# Resonator_ISTA.net
KiCad netlist of a schematic drawn in EAGLE
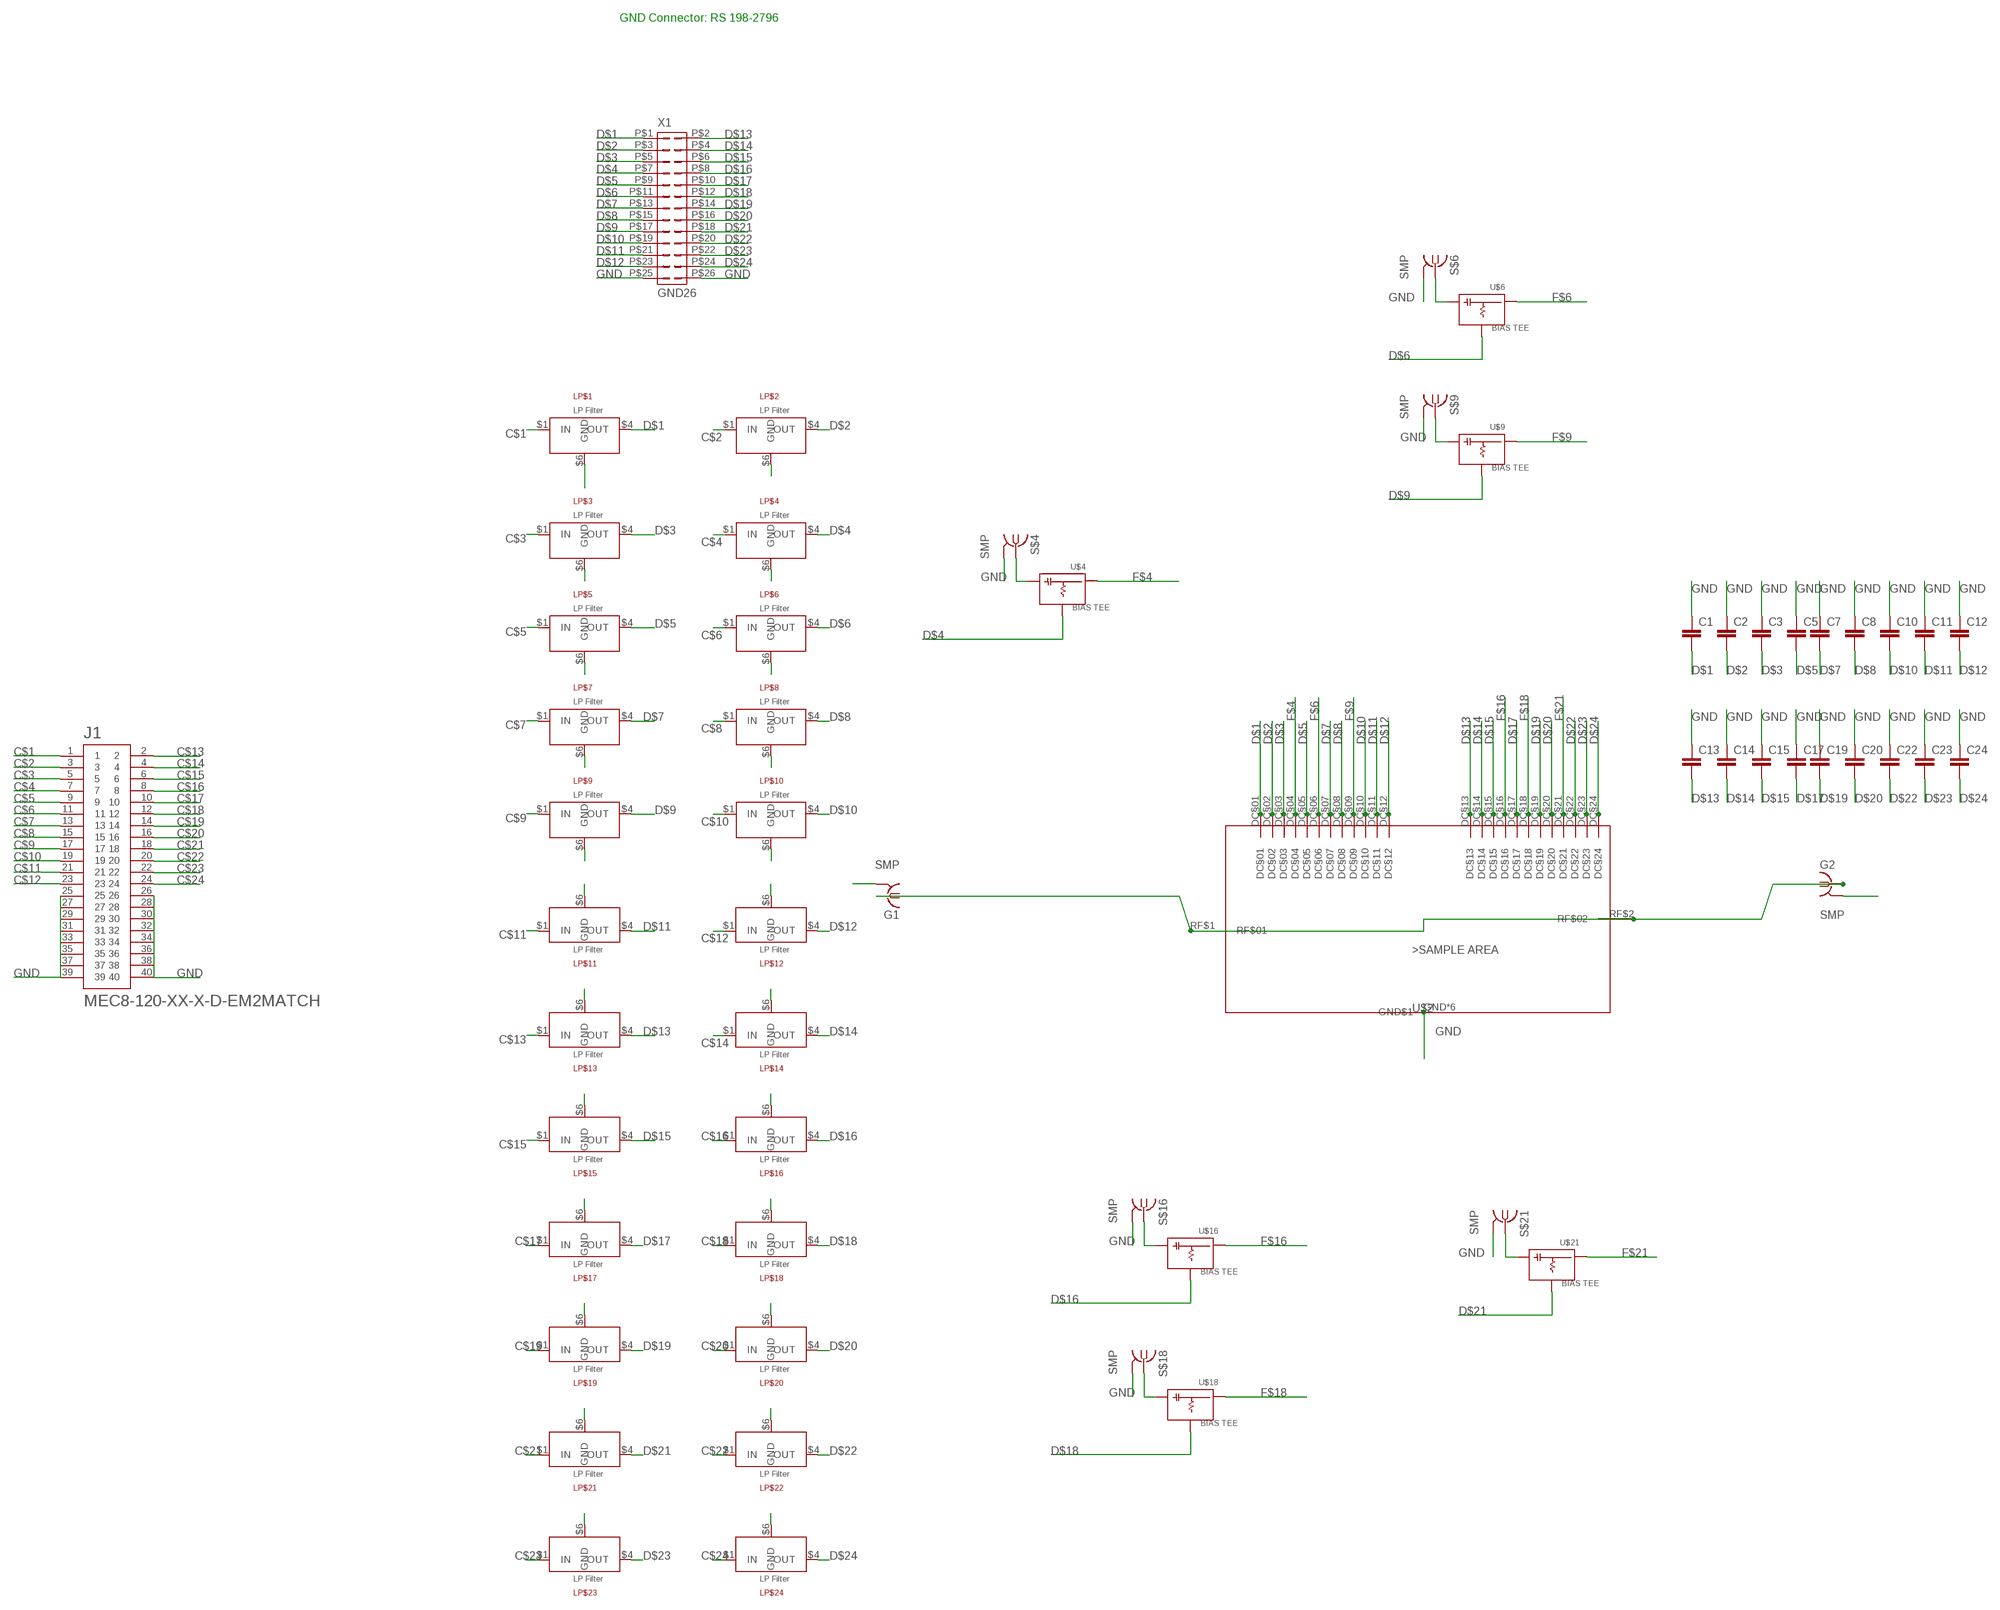
[diagram p0: schematic, sheet 1]

(export (version "E")
  (design (tool "Eeschema 10.0.6"))
  (components
    (comp (ref "C1")
      (value "C-EUC0805K")
      (footprint "eagle-import:C0805K")
      (libsource (lib "eagle-import") (part "C-EUC0805K"))
    )
    (comp (ref "C2")
      (value "C-EUC0805K")
      (footprint "eagle-import:C0805K")
      (libsource (lib "eagle-import") (part "C-EUC0805K"))
    )
    (comp (ref "C3")
      (value "C-EUC0805K")
      (footprint "eagle-import:C0805K")
      (libsource (lib "eagle-import") (part "C-EUC0805K"))
    )
    (comp (ref "C5")
      (value "C-EUC0805K")
      (footprint "eagle-import:C0805K")
      (libsource (lib "eagle-import") (part "C-EUC0805K"))
    )
    (comp (ref "C7")
      (value "C-EUC0805K")
      (footprint "eagle-import:C0805K")
      (libsource (lib "eagle-import") (part "C-EUC0805K"))
    )
    (comp (ref "C8")
      (value "C-EUC0805K")
      (footprint "eagle-import:C0805K")
      (libsource (lib "eagle-import") (part "C-EUC0805K"))
    )
    (comp (ref "C10")
      (value "C-EUC0805K")
      (footprint "eagle-import:C0805K")
      (libsource (lib "eagle-import") (part "C-EUC0805K"))
    )
    (comp (ref "C11")
      (value "C-EUC0805K")
      (footprint "eagle-import:C0805K")
      (libsource (lib "eagle-import") (part "C-EUC0805K"))
    )
    (comp (ref "C12")
      (value "C-EUC0805K")
      (footprint "eagle-import:C0805K")
      (libsource (lib "eagle-import") (part "C-EUC0805K"))
    )
    (comp (ref "C13")
      (value "C-EUC0805K")
      (footprint "eagle-import:C0805K")
      (libsource (lib "eagle-import") (part "C-EUC0805K"))
    )
    (comp (ref "C14")
      (value "C-EUC0805K")
      (footprint "eagle-import:C0805K")
      (libsource (lib "eagle-import") (part "C-EUC0805K"))
    )
    (comp (ref "C15")
      (value "C-EUC0805K")
      (footprint "eagle-import:C0805K")
      (libsource (lib "eagle-import") (part "C-EUC0805K"))
    )
    (comp (ref "C17")
      (value "C-EUC0805K")
      (footprint "eagle-import:C0805K")
      (libsource (lib "eagle-import") (part "C-EUC0805K"))
    )
    (comp (ref "C19")
      (value "C-EUC0805K")
      (footprint "eagle-import:C0805K")
      (libsource (lib "eagle-import") (part "C-EUC0805K"))
    )
    (comp (ref "C20")
      (value "C-EUC0805K")
      (footprint "eagle-import:C0805K")
      (libsource (lib "eagle-import") (part "C-EUC0805K"))
    )
    (comp (ref "C22")
      (value "C-EUC0805K")
      (footprint "eagle-import:C0805K")
      (libsource (lib "eagle-import") (part "C-EUC0805K"))
    )
    (comp (ref "C23")
      (value "C-EUC0805K")
      (footprint "eagle-import:C0805K")
      (libsource (lib "eagle-import") (part "C-EUC0805K"))
    )
    (comp (ref "C24")
      (value "C-EUC0805K")
      (footprint "eagle-import:C0805K")
      (libsource (lib "eagle-import") (part "C-EUC0805K"))
    )
    (comp (ref "G1")
      (value "MC-921")
      (footprint "eagle-import:SMP_STRAIGHT_MINI_WIDE_V1_01_ROUND")
      (libsource (lib "eagle-import") (part "MC-921"))
    )
    (comp (ref "G2")
      (value "MC-921")
      (footprint "eagle-import:SMP_STRAIGHT_MINI_WIDE_V1_01_ROUND")
      (libsource (lib "eagle-import") (part "MC-921"))
    )
    (comp (ref "J1")
      (value "MEC8-120-XX-X-D-EM2MATCH")
      (footprint "eagle-import:SAMTEC_MEC8-120-XX-X-D-EM2_MATCH")
      (libsource (lib "eagle-import") (part "MEC8-120-XX-X-D-EM2MATCH"))
    )
    (comp (ref "LP$1")
      (value "LP-FILTER/1-STAGETOP")
      (footprint "eagle-import:LP-FILTER_1_STAGE_OS_0603_TOP")
      (libsource (lib "eagle-import") (part "LP-FILTER/1-STAGETOP"))
    )
    (comp (ref "LP$2")
      (value "LP-FILTER/1-STAGETOP")
      (footprint "eagle-import:LP-FILTER_1_STAGE_OS_0603_TOP")
      (libsource (lib "eagle-import") (part "LP-FILTER/1-STAGETOP"))
    )
    (comp (ref "LP$3")
      (value "LP-FILTER/1-STAGEBOT")
      (footprint "eagle-import:LP-FILTER_1_STAGE_OS_0603_BOTTOM")
      (libsource (lib "eagle-import") (part "LP-FILTER/1-STAGEBOT"))
    )
    (comp (ref "LP$4")
      (value "LP-FILTER/1-STAGEBOT")
      (footprint "eagle-import:LP-FILTER_1_STAGE_OS_0603_BOTTOM")
      (libsource (lib "eagle-import") (part "LP-FILTER/1-STAGEBOT"))
    )
    (comp (ref "LP$5")
      (value "LP-FILTER/1-STAGEBOT")
      (footprint "eagle-import:LP-FILTER_1_STAGE_OS_0603_BOTTOM")
      (libsource (lib "eagle-import") (part "LP-FILTER/1-STAGEBOT"))
    )
    (comp (ref "LP$6")
      (value "LP-FILTER/1-STAGEBOT")
      (footprint "eagle-import:LP-FILTER_1_STAGE_OS_0603_BOTTOM")
      (libsource (lib "eagle-import") (part "LP-FILTER/1-STAGEBOT"))
    )
    (comp (ref "LP$7")
      (value "LP-FILTER/1-STAGEBOT")
      (footprint "eagle-import:LP-FILTER_1_STAGE_OS_0603_BOTTOM")
      (libsource (lib "eagle-import") (part "LP-FILTER/1-STAGEBOT"))
    )
    (comp (ref "LP$8")
      (value "LP-FILTER/1-STAGEBOT")
      (footprint "eagle-import:LP-FILTER_1_STAGE_OS_0603_BOTTOM")
      (libsource (lib "eagle-import") (part "LP-FILTER/1-STAGEBOT"))
    )
    (comp (ref "LP$9")
      (value "LP-FILTER/1-STAGETOP")
      (footprint "eagle-import:LP-FILTER_1_STAGE_OS_0603_TOP")
      (libsource (lib "eagle-import") (part "LP-FILTER/1-STAGETOP"))
    )
    (comp (ref "LP$10")
      (value "LP-FILTER/1-STAGETOP")
      (footprint "eagle-import:LP-FILTER_1_STAGE_OS_0603_TOP")
      (libsource (lib "eagle-import") (part "LP-FILTER/1-STAGETOP"))
    )
    (comp (ref "LP$11")
      (value "LP-FILTER/1-STAGETOP")
      (footprint "eagle-import:LP-FILTER_1_STAGE_OS_0603_TOP")
      (libsource (lib "eagle-import") (part "LP-FILTER/1-STAGETOP"))
    )
    (comp (ref "LP$12")
      (value "LP-FILTER/1-STAGETOP")
      (footprint "eagle-import:LP-FILTER_1_STAGE_OS_0603_TOP")
      (libsource (lib "eagle-import") (part "LP-FILTER/1-STAGETOP"))
    )
    (comp (ref "LP$13")
      (value "LP-FILTER/1-STAGETOP")
      (footprint "eagle-import:LP-FILTER_1_STAGE_OS_0603_TOP")
      (libsource (lib "eagle-import") (part "LP-FILTER/1-STAGETOP"))
    )
    (comp (ref "LP$14")
      (value "LP-FILTER/1-STAGETOP")
      (footprint "eagle-import:LP-FILTER_1_STAGE_OS_0603_TOP")
      (libsource (lib "eagle-import") (part "LP-FILTER/1-STAGETOP"))
    )
    (comp (ref "LP$15")
      (value "LP-FILTER/1-STAGETOP")
      (footprint "eagle-import:LP-FILTER_1_STAGE_OS_0603_TOP")
      (libsource (lib "eagle-import") (part "LP-FILTER/1-STAGETOP"))
    )
    (comp (ref "LP$16")
      (value "LP-FILTER/1-STAGETOP")
      (footprint "eagle-import:LP-FILTER_1_STAGE_OS_0603_TOP")
      (libsource (lib "eagle-import") (part "LP-FILTER/1-STAGETOP"))
    )
    (comp (ref "LP$17")
      (value "LP-FILTER/1-STAGETOP")
      (footprint "eagle-import:LP-FILTER_1_STAGE_OS_0603_TOP")
      (libsource (lib "eagle-import") (part "LP-FILTER/1-STAGETOP"))
    )
    (comp (ref "LP$18")
      (value "LP-FILTER/1-STAGETOP")
      (footprint "eagle-import:LP-FILTER_1_STAGE_OS_0603_TOP")
      (libsource (lib "eagle-import") (part "LP-FILTER/1-STAGETOP"))
    )
    (comp (ref "LP$19")
      (value "LP-FILTER/1-STAGETOP")
      (footprint "eagle-import:LP-FILTER_1_STAGE_OS_0603_TOP")
      (libsource (lib "eagle-import") (part "LP-FILTER/1-STAGETOP"))
    )
    (comp (ref "LP$20")
      (value "LP-FILTER/1-STAGETOP")
      (footprint "eagle-import:LP-FILTER_1_STAGE_OS_0603_TOP")
      (libsource (lib "eagle-import") (part "LP-FILTER/1-STAGETOP"))
    )
    (comp (ref "LP$21")
      (value "LP-FILTER/1-STAGETOP")
      (footprint "eagle-import:LP-FILTER_1_STAGE_OS_0603_TOP")
      (libsource (lib "eagle-import") (part "LP-FILTER/1-STAGETOP"))
    )
    (comp (ref "LP$22")
      (value "LP-FILTER/1-STAGETOP")
      (footprint "eagle-import:LP-FILTER_1_STAGE_OS_0603_TOP")
      (libsource (lib "eagle-import") (part "LP-FILTER/1-STAGETOP"))
    )
    (comp (ref "LP$23")
      (value "LP-FILTER/1-STAGETOP")
      (footprint "eagle-import:LP-FILTER_1_STAGE_OS_0603_TOP")
      (libsource (lib "eagle-import") (part "LP-FILTER/1-STAGETOP"))
    )
    (comp (ref "LP$24")
      (value "LP-FILTER/1-STAGETOP")
      (footprint "eagle-import:LP-FILTER_1_STAGE_OS_0603_TOP")
      (libsource (lib "eagle-import") (part "LP-FILTER/1-STAGETOP"))
    )
    (comp (ref "S$4")
      (value "MC-921")
      (footprint "eagle-import:SMP_STRAIGHT_MINI_WIDE_V1_01_ROUND")
      (libsource (lib "eagle-import") (part "MC-921"))
    )
    (comp (ref "S$6")
      (value "MC-921")
      (footprint "eagle-import:SMP_STRAIGHT_MINI_WIDE_V1_01_ROUND")
      (libsource (lib "eagle-import") (part "MC-921"))
    )
    (comp (ref "S$9")
      (value "MC-921")
      (footprint "eagle-import:SMP_STRAIGHT_MINI_WIDE_V1_01_ROUND")
      (libsource (lib "eagle-import") (part "MC-921"))
    )
    (comp (ref "S$16")
      (value "MC-921")
      (footprint "eagle-import:SMP_STRAIGHT_MINI_WIDE_V1_01_ROUND")
      (libsource (lib "eagle-import") (part "MC-921"))
    )
    (comp (ref "S$18")
      (value "MC-921")
      (footprint "eagle-import:SMP_STRAIGHT_MINI_WIDE_V1_01_ROUND")
      (libsource (lib "eagle-import") (part "MC-921"))
    )
    (comp (ref "S$21")
      (value "MC-921")
      (footprint "eagle-import:SMP_STRAIGHT_MINI_WIDE_V1_01_ROUND")
      (libsource (lib "eagle-import") (part "MC-921"))
    )
    (comp (ref "U$2")
      (value "24DC+4FAST+2RF_NO_HOLETEST")
      (footprint "eagle-import:24DC+4FASTGATE+2RF_6.0X6.0_V2.11")
      (libsource (lib "eagle-import") (part "24DC+4FAST+2RF_NO_HOLETEST"))
    )
    (comp (ref "U$4")
      (value "BIASTEETHINUP")
      (footprint "eagle-import:BIAS_TEE_UP_0603_THIN")
      (libsource (lib "eagle-import") (part "BIASTEETHINUP"))
    )
    (comp (ref "U$6")
      (value "BIASTEETHIN")
      (footprint "eagle-import:BIAS_TEE_DOWN_0603_THIN")
      (libsource (lib "eagle-import") (part "BIASTEETHIN"))
    )
    (comp (ref "U$9")
      (value "BIASTEETHIN")
      (footprint "eagle-import:BIAS_TEE_DOWN_0603_THIN")
      (libsource (lib "eagle-import") (part "BIASTEETHIN"))
    )
    (comp (ref "U$16")
      (value "BIASTEETHINUP")
      (footprint "eagle-import:BIAS_TEE_UP_0603_THIN")
      (libsource (lib "eagle-import") (part "BIASTEETHINUP"))
    )
    (comp (ref "U$18")
      (value "BIASTEETHINUP")
      (footprint "eagle-import:BIAS_TEE_UP_0603_THIN")
      (libsource (lib "eagle-import") (part "BIASTEETHINUP"))
    )
    (comp (ref "U$21")
      (value "BIASTEETHIN")
      (footprint "eagle-import:BIAS_TEE_DOWN_0603_THIN")
      (libsource (lib "eagle-import") (part "BIASTEETHIN"))
    )
    (comp (ref "X1")
      (value "GND26")
      (footprint "eagle-import:SMD2X13")
      (libsource (lib "eagle-import") (part "GND26"))
    )
  )
  (nets
    (net (code "1") (name "/C$1") (class "Default")
      (node (ref "J1") (pin "1") (pinfunction "1_1") (pintype "passive"))
      (node (ref "LP$1") (pin "$1") (pinfunction "IN_$1") (pintype "bidirectional"))
    )
    (net (code "2") (name "/C$2") (class "Default")
      (node (ref "J1") (pin "3") (pinfunction "3_3") (pintype "passive"))
      (node (ref "LP$2") (pin "$1") (pinfunction "IN_$1") (pintype "bidirectional"))
    )
    (net (code "3") (name "/C$3") (class "Default")
      (node (ref "J1") (pin "5") (pinfunction "5_5") (pintype "passive"))
      (node (ref "LP$3") (pin "$1") (pinfunction "IN_$1") (pintype "bidirectional"))
    )
    (net (code "4") (name "/C$4") (class "Default")
      (node (ref "J1") (pin "7") (pinfunction "7_7") (pintype "passive"))
      (node (ref "LP$4") (pin "$1") (pinfunction "IN_$1") (pintype "bidirectional"))
    )
    (net (code "5") (name "/C$5") (class "Default")
      (node (ref "J1") (pin "9") (pinfunction "9_9") (pintype "passive"))
      (node (ref "LP$5") (pin "$1") (pinfunction "IN_$1") (pintype "bidirectional"))
    )
    (net (code "6") (name "/C$6") (class "Default")
      (node (ref "J1") (pin "11") (pinfunction "11_11") (pintype "passive"))
      (node (ref "LP$6") (pin "$1") (pinfunction "IN_$1") (pintype "bidirectional"))
    )
    (net (code "7") (name "/C$7") (class "Default")
      (node (ref "J1") (pin "13") (pinfunction "13_13") (pintype "passive"))
      (node (ref "LP$7") (pin "$1") (pinfunction "IN_$1") (pintype "bidirectional"))
    )
    (net (code "8") (name "/C$8") (class "Default")
      (node (ref "J1") (pin "15") (pinfunction "15_15") (pintype "passive"))
      (node (ref "LP$8") (pin "$1") (pinfunction "IN_$1") (pintype "bidirectional"))
    )
    (net (code "9") (name "/C$9") (class "Default")
      (node (ref "J1") (pin "17") (pinfunction "17_17") (pintype "passive"))
      (node (ref "LP$9") (pin "$1") (pinfunction "IN_$1") (pintype "bidirectional"))
    )
    (net (code "10") (name "/C$10") (class "Default")
      (node (ref "J1") (pin "19") (pinfunction "19_19") (pintype "passive"))
      (node (ref "LP$10") (pin "$1") (pinfunction "IN_$1") (pintype "bidirectional"))
    )
    (net (code "11") (name "/C$11") (class "Default")
      (node (ref "J1") (pin "21") (pinfunction "21_21") (pintype "passive"))
      (node (ref "LP$11") (pin "$1") (pinfunction "IN_$1") (pintype "bidirectional"))
    )
    (net (code "12") (name "/C$12") (class "Default")
      (node (ref "J1") (pin "23") (pinfunction "23_23") (pintype "passive"))
      (node (ref "LP$12") (pin "$1") (pinfunction "IN_$1") (pintype "bidirectional"))
    )
    (net (code "13") (name "/C$13") (class "Default")
      (node (ref "J1") (pin "2") (pinfunction "2_2") (pintype "passive"))
      (node (ref "LP$13") (pin "$1") (pinfunction "IN_$1") (pintype "bidirectional"))
    )
    (net (code "14") (name "/C$14") (class "Default")
      (node (ref "J1") (pin "4") (pinfunction "4_4") (pintype "passive"))
      (node (ref "LP$14") (pin "$1") (pinfunction "IN_$1") (pintype "bidirectional"))
    )
    (net (code "15") (name "/C$15") (class "Default")
      (node (ref "J1") (pin "6") (pinfunction "6_6") (pintype "passive"))
      (node (ref "LP$15") (pin "$1") (pinfunction "IN_$1") (pintype "bidirectional"))
    )
    (net (code "16") (name "/C$16") (class "Default")
      (node (ref "J1") (pin "8") (pinfunction "8_8") (pintype "passive"))
      (node (ref "LP$16") (pin "$1") (pinfunction "IN_$1") (pintype "bidirectional"))
    )
    (net (code "17") (name "/C$17") (class "Default")
      (node (ref "J1") (pin "10") (pinfunction "10_10") (pintype "passive"))
      (node (ref "LP$17") (pin "$1") (pinfunction "IN_$1") (pintype "bidirectional"))
    )
    (net (code "18") (name "/C$18") (class "Default")
      (node (ref "J1") (pin "12") (pinfunction "12_12") (pintype "passive"))
      (node (ref "LP$18") (pin "$1") (pinfunction "IN_$1") (pintype "bidirectional"))
    )
    (net (code "19") (name "/C$19") (class "Default")
      (node (ref "J1") (pin "14") (pinfunction "14_14") (pintype "passive"))
      (node (ref "LP$19") (pin "$1") (pinfunction "IN_$1") (pintype "bidirectional"))
    )
    (net (code "20") (name "/C$20") (class "Default")
      (node (ref "J1") (pin "16") (pinfunction "16_16") (pintype "passive"))
      (node (ref "LP$20") (pin "$1") (pinfunction "IN_$1") (pintype "bidirectional"))
    )
    (net (code "21") (name "/C$21") (class "Default")
      (node (ref "J1") (pin "18") (pinfunction "18_18") (pintype "passive"))
      (node (ref "LP$21") (pin "$1") (pinfunction "IN_$1") (pintype "bidirectional"))
    )
    (net (code "22") (name "/C$22") (class "Default")
      (node (ref "J1") (pin "20") (pinfunction "20_20") (pintype "passive"))
      (node (ref "LP$22") (pin "$1") (pinfunction "IN_$1") (pintype "bidirectional"))
    )
    (net (code "23") (name "/C$23") (class "Default")
      (node (ref "J1") (pin "22") (pinfunction "22_22") (pintype "passive"))
      (node (ref "LP$23") (pin "$1") (pinfunction "IN_$1") (pintype "bidirectional"))
    )
    (net (code "24") (name "/C$24") (class "Default")
      (node (ref "J1") (pin "24") (pinfunction "24_24") (pintype "passive"))
      (node (ref "LP$24") (pin "$1") (pinfunction "IN_$1") (pintype "bidirectional"))
    )
    (net (code "25") (name "/D$1") (class "Default")
      (node (ref "C1") (pin "2") (pinfunction "2_2") (pintype "passive"))
      (node (ref "LP$1") (pin "$4") (pinfunction "OUT_$4") (pintype "bidirectional"))
      (node (ref "U$2") (pin "DC§01") (pinfunction "DC§01_DC§01") (pintype "bidirectional"))
      (node (ref "X1") (pin "P$1") (pinfunction "1_P$1") (pintype "passive"))
    )
    (net (code "26") (name "/D$2") (class "Default")
      (node (ref "C2") (pin "2") (pinfunction "2_2") (pintype "passive"))
      (node (ref "LP$2") (pin "$4") (pinfunction "OUT_$4") (pintype "bidirectional"))
      (node (ref "U$2") (pin "DC§02") (pinfunction "DC§02_DC§02") (pintype "bidirectional"))
      (node (ref "X1") (pin "P$3") (pinfunction "3_P$3") (pintype "passive"))
    )
    (net (code "27") (name "/D$3") (class "Default")
      (node (ref "C3") (pin "2") (pinfunction "2_2") (pintype "passive"))
      (node (ref "LP$3") (pin "$4") (pinfunction "OUT_$4") (pintype "bidirectional"))
      (node (ref "U$2") (pin "DC§03") (pinfunction "DC§03_DC§03") (pintype "bidirectional"))
      (node (ref "X1") (pin "P$5") (pinfunction "5_P$5") (pintype "passive"))
    )
    (net (code "28") (name "/D$4") (class "Default")
      (node (ref "LP$4") (pin "$4") (pinfunction "OUT_$4") (pintype "bidirectional"))
      (node (ref "U$4") (pin "LF") (pinfunction "LF_LF") (pintype "bidirectional"))
      (node (ref "X1") (pin "P$7") (pinfunction "7_P$7") (pintype "passive"))
    )
    (net (code "29") (name "/D$5") (class "Default")
      (node (ref "C5") (pin "2") (pinfunction "2_2") (pintype "passive"))
      (node (ref "LP$5") (pin "$4") (pinfunction "OUT_$4") (pintype "bidirectional"))
      (node (ref "U$2") (pin "DC§05") (pinfunction "DC§05_DC§05") (pintype "bidirectional"))
      (node (ref "X1") (pin "P$9") (pinfunction "9_P$9") (pintype "passive"))
    )
    (net (code "30") (name "/D$6") (class "Default")
      (node (ref "LP$6") (pin "$4") (pinfunction "OUT_$4") (pintype "bidirectional"))
      (node (ref "U$6") (pin "LF") (pinfunction "LF_LF") (pintype "bidirectional"))
      (node (ref "X1") (pin "P$11") (pinfunction "11_P$11") (pintype "passive"))
    )
    (net (code "31") (name "/D$7") (class "Default")
      (node (ref "C7") (pin "2") (pinfunction "2_2") (pintype "passive"))
      (node (ref "LP$7") (pin "$4") (pinfunction "OUT_$4") (pintype "bidirectional"))
      (node (ref "U$2") (pin "DC§07") (pinfunction "DC§07_DC§07") (pintype "bidirectional"))
      (node (ref "X1") (pin "P$13") (pinfunction "13_P$13") (pintype "passive"))
    )
    (net (code "32") (name "/D$8") (class "Default")
      (node (ref "C8") (pin "2") (pinfunction "2_2") (pintype "passive"))
      (node (ref "LP$8") (pin "$4") (pinfunction "OUT_$4") (pintype "bidirectional"))
      (node (ref "U$2") (pin "DC§08") (pinfunction "DC§08_DC§08") (pintype "bidirectional"))
      (node (ref "X1") (pin "P$15") (pinfunction "15_P$15") (pintype "passive"))
    )
    (net (code "33") (name "/D$9") (class "Default")
      (node (ref "LP$9") (pin "$4") (pinfunction "OUT_$4") (pintype "bidirectional"))
      (node (ref "U$9") (pin "LF") (pinfunction "LF_LF") (pintype "bidirectional"))
      (node (ref "X1") (pin "P$17") (pinfunction "17_P$17") (pintype "passive"))
    )
    (net (code "34") (name "/D$10") (class "Default")
      (node (ref "C10") (pin "2") (pinfunction "2_2") (pintype "passive"))
      (node (ref "LP$10") (pin "$4") (pinfunction "OUT_$4") (pintype "bidirectional"))
      (node (ref "U$2") (pin "DC§10") (pinfunction "DC§10_DC§10") (pintype "bidirectional"))
      (node (ref "X1") (pin "P$19") (pinfunction "19_P$19") (pintype "passive"))
    )
    (net (code "35") (name "/D$11") (class "Default")
      (node (ref "C11") (pin "2") (pinfunction "2_2") (pintype "passive"))
      (node (ref "LP$11") (pin "$4") (pinfunction "OUT_$4") (pintype "bidirectional"))
      (node (ref "U$2") (pin "DC§11") (pinfunction "DC§11_DC§11") (pintype "bidirectional"))
      (node (ref "X1") (pin "P$21") (pinfunction "21_P$21") (pintype "passive"))
    )
    (net (code "36") (name "/D$12") (class "Default")
      (node (ref "C12") (pin "2") (pinfunction "2_2") (pintype "passive"))
      (node (ref "LP$12") (pin "$4") (pinfunction "OUT_$4") (pintype "bidirectional"))
      (node (ref "U$2") (pin "DC§12") (pinfunction "DC§12_DC§12") (pintype "bidirectional"))
      (node (ref "X1") (pin "P$23") (pinfunction "23_P$23") (pintype "passive"))
    )
    (net (code "37") (name "/D$13") (class "Default")
      (node (ref "C13") (pin "2") (pinfunction "2_2") (pintype "passive"))
      (node (ref "LP$13") (pin "$4") (pinfunction "OUT_$4") (pintype "bidirectional"))
      (node (ref "U$2") (pin "DC§13") (pinfunction "DC§13_DC§13") (pintype "bidirectional"))
      (node (ref "X1") (pin "P$2") (pinfunction "2_P$2") (pintype "passive"))
    )
    (net (code "38") (name "/D$14") (class "Default")
      (node (ref "C14") (pin "2") (pinfunction "2_2") (pintype "passive"))
      (node (ref "LP$14") (pin "$4") (pinfunction "OUT_$4") (pintype "bidirectional"))
      (node (ref "U$2") (pin "DC§14") (pinfunction "DC§14_DC§14") (pintype "bidirectional"))
      (node (ref "X1") (pin "P$4") (pinfunction "4_P$4") (pintype "passive"))
    )
    (net (code "39") (name "/D$15") (class "Default")
      (node (ref "C15") (pin "2") (pinfunction "2_2") (pintype "passive"))
      (node (ref "LP$15") (pin "$4") (pinfunction "OUT_$4") (pintype "bidirectional"))
      (node (ref "U$2") (pin "DC§15") (pinfunction "DC§15_DC§15") (pintype "bidirectional"))
      (node (ref "X1") (pin "P$6") (pinfunction "6_P$6") (pintype "passive"))
    )
    (net (code "40") (name "/D$16") (class "Default")
      (node (ref "LP$16") (pin "$4") (pinfunction "OUT_$4") (pintype "bidirectional"))
      (node (ref "U$16") (pin "LF") (pinfunction "LF_LF") (pintype "bidirectional"))
      (node (ref "X1") (pin "P$8") (pinfunction "8_P$8") (pintype "passive"))
    )
    (net (code "41") (name "/D$17") (class "Default")
      (node (ref "C17") (pin "2") (pinfunction "2_2") (pintype "passive"))
      (node (ref "LP$17") (pin "$4") (pinfunction "OUT_$4") (pintype "bidirectional"))
      (node (ref "U$2") (pin "DC§17") (pinfunction "DC§17_DC§17") (pintype "bidirectional"))
      (node (ref "X1") (pin "P$10") (pinfunction "10_P$10") (pintype "passive"))
    )
    (net (code "42") (name "/D$18") (class "Default")
      (node (ref "LP$18") (pin "$4") (pinfunction "OUT_$4") (pintype "bidirectional"))
      (node (ref "U$18") (pin "LF") (pinfunction "LF_LF") (pintype "bidirectional"))
      (node (ref "X1") (pin "P$12") (pinfunction "12_P$12") (pintype "passive"))
    )
    (net (code "43") (name "/D$19") (class "Default")
      (node (ref "C19") (pin "2") (pinfunction "2_2") (pintype "passive"))
      (node (ref "LP$19") (pin "$4") (pinfunction "OUT_$4") (pintype "bidirectional"))
      (node (ref "U$2") (pin "DC§19") (pinfunction "DC§19_DC§19") (pintype "bidirectional"))
      (node (ref "X1") (pin "P$14") (pinfunction "14_P$14") (pintype "passive"))
    )
    (net (code "44") (name "/D$20") (class "Default")
      (node (ref "C20") (pin "2") (pinfunction "2_2") (pintype "passive"))
      (node (ref "LP$20") (pin "$4") (pinfunction "OUT_$4") (pintype "bidirectional"))
      (node (ref "U$2") (pin "DC§20") (pinfunction "DC§20_DC§20") (pintype "bidirectional"))
      (node (ref "X1") (pin "P$16") (pinfunction "16_P$16") (pintype "passive"))
    )
    (net (code "45") (name "/D$21") (class "Default")
      (node (ref "LP$21") (pin "$4") (pinfunction "OUT_$4") (pintype "bidirectional"))
      (node (ref "U$21") (pin "LF") (pinfunction "LF_LF") (pintype "bidirectional"))
      (node (ref "X1") (pin "P$18") (pinfunction "18_P$18") (pintype "passive"))
    )
    (net (code "46") (name "/D$22") (class "Default")
      (node (ref "C22") (pin "2") (pinfunction "2_2") (pintype "passive"))
      (node (ref "LP$22") (pin "$4") (pinfunction "OUT_$4") (pintype "bidirectional"))
      (node (ref "U$2") (pin "DC§22") (pinfunction "DC§22_DC§22") (pintype "bidirectional"))
      (node (ref "X1") (pin "P$20") (pinfunction "20_P$20") (pintype "passive"))
    )
    (net (code "47") (name "/D$23") (class "Default")
      (node (ref "C23") (pin "2") (pinfunction "2_2") (pintype "passive"))
      (node (ref "LP$23") (pin "$4") (pinfunction "OUT_$4") (pintype "bidirectional"))
      (node (ref "U$2") (pin "DC§23") (pinfunction "DC§23_DC§23") (pintype "bidirectional"))
      (node (ref "X1") (pin "P$22") (pinfunction "22_P$22") (pintype "passive"))
    )
    (net (code "48") (name "/D$24") (class "Default")
      (node (ref "C24") (pin "2") (pinfunction "2_2") (pintype "passive"))
      (node (ref "LP$24") (pin "$4") (pinfunction "OUT_$4") (pintype "bidirectional"))
      (node (ref "U$2") (pin "DC§24") (pinfunction "DC§24_DC§24") (pintype "bidirectional"))
      (node (ref "X1") (pin "P$24") (pinfunction "24_P$24") (pintype "passive"))
    )
    (net (code "49") (name "/F$4") (class "Default")
      (node (ref "U$2") (pin "DC§04") (pinfunction "DC§04_DC§04") (pintype "bidirectional"))
      (node (ref "U$4") (pin "OUT") (pinfunction "OUT_OUT") (pintype "bidirectional"))
    )
    (net (code "50") (name "/F$6") (class "Default")
      (node (ref "U$2") (pin "DC§06") (pinfunction "DC§06_DC§06") (pintype "bidirectional"))
      (node (ref "U$6") (pin "OUT") (pinfunction "OUT_OUT") (pintype "bidirectional"))
    )
    (net (code "51") (name "/F$9") (class "Default")
      (node (ref "U$2") (pin "DC§09") (pinfunction "DC§09_DC§09") (pintype "bidirectional"))
      (node (ref "U$9") (pin "OUT") (pinfunction "OUT_OUT") (pintype "bidirectional"))
    )
    (net (code "52") (name "/F$16") (class "Default")
      (node (ref "U$16") (pin "OUT") (pinfunction "OUT_OUT") (pintype "bidirectional"))
      (node (ref "U$2") (pin "DC§16") (pinfunction "DC§16_DC§16") (pintype "bidirectional"))
    )
    (net (code "53") (name "/F$18") (class "Default")
      (node (ref "U$18") (pin "OUT") (pinfunction "OUT_OUT") (pintype "bidirectional"))
      (node (ref "U$2") (pin "DC§18") (pinfunction "DC§18_DC§18") (pintype "bidirectional"))
    )
    (net (code "54") (name "/F$21") (class "Default")
      (node (ref "U$2") (pin "DC§21") (pinfunction "DC§21_DC§21") (pintype "bidirectional"))
      (node (ref "U$21") (pin "OUT") (pinfunction "OUT_OUT") (pintype "bidirectional"))
    )
    (net (code "55") (name "/GND") (class "Default")
      (node (ref "C1") (pin "1") (pinfunction "1_1") (pintype "passive"))
      (node (ref "C10") (pin "1") (pinfunction "1_1") (pintype "passive"))
      (node (ref "C11") (pin "1") (pinfunction "1_1") (pintype "passive"))
      (node (ref "C12") (pin "1") (pinfunction "1_1") (pintype "passive"))
      (node (ref "C13") (pin "1") (pinfunction "1_1") (pintype "passive"))
      (node (ref "C14") (pin "1") (pinfunction "1_1") (pintype "passive"))
      (node (ref "C15") (pin "1") (pinfunction "1_1") (pintype "passive"))
      (node (ref "C17") (pin "1") (pinfunction "1_1") (pintype "passive"))
      (node (ref "C19") (pin "1") (pinfunction "1_1") (pintype "passive"))
      (node (ref "C2") (pin "1") (pinfunction "1_1") (pintype "passive"))
      (node (ref "C20") (pin "1") (pinfunction "1_1") (pintype "passive"))
      (node (ref "C22") (pin "1") (pinfunction "1_1") (pintype "passive"))
      (node (ref "C23") (pin "1") (pinfunction "1_1") (pintype "passive"))
      (node (ref "C24") (pin "1") (pinfunction "1_1") (pintype "passive"))
      (node (ref "C3") (pin "1") (pinfunction "1_1") (pintype "passive"))
      (node (ref "C5") (pin "1") (pinfunction "1_1") (pintype "passive"))
      (node (ref "C7") (pin "1") (pinfunction "1_1") (pintype "passive"))
      (node (ref "C8") (pin "1") (pinfunction "1_1") (pintype "passive"))
      (node (ref "G1") (pin "GND") (pinfunction "GND_GND") (pintype "passive"))
      (node (ref "G1") (pin "GND@1") (pinfunction "GND_GND@1") (pintype "passive"))
      (node (ref "G2") (pin "GND") (pinfunction "GND_GND") (pintype "passive"))
      (node (ref "G2") (pin "GND@1") (pinfunction "GND_GND@1") (pintype "passive"))
      (node (ref "J1") (pin "25") (pinfunction "25_25") (pintype "passive"))
      (node (ref "J1") (pin "26") (pinfunction "26_26") (pintype "passive"))
      (node (ref "J1") (pin "27") (pinfunction "27_27") (pintype "passive"))
      (node (ref "J1") (pin "28") (pinfunction "28_28") (pintype "passive"))
      (node (ref "J1") (pin "29") (pinfunction "29_29") (pintype "passive"))
      (node (ref "J1") (pin "30") (pinfunction "30_30") (pintype "passive"))
      (node (ref "J1") (pin "31") (pinfunction "31_31") (pintype "passive"))
      (node (ref "J1") (pin "32") (pinfunction "32_32") (pintype "passive"))
      (node (ref "J1") (pin "33") (pinfunction "33_33") (pintype "passive"))
      (node (ref "J1") (pin "34") (pinfunction "34_34") (pintype "passive"))
      (node (ref "J1") (pin "35") (pinfunction "35_35") (pintype "passive"))
      (node (ref "J1") (pin "36") (pinfunction "36_36") (pintype "passive"))
      (node (ref "J1") (pin "37") (pinfunction "37_37") (pintype "passive"))
      (node (ref "J1") (pin "38") (pinfunction "38_38") (pintype "passive"))
      (node (ref "J1") (pin "39") (pinfunction "39_39") (pintype "passive"))
      (node (ref "J1") (pin "40") (pinfunction "40_40") (pintype "passive"))
      (node (ref "LP$1") (pin "$6") (pinfunction "GND_$6") (pintype "bidirectional"))
      (node (ref "LP$10") (pin "$6") (pinfunction "GND_$6") (pintype "bidirectional"))
      (node (ref "LP$11") (pin "$6") (pinfunction "GND_$6") (pintype "bidirectional"))
      (node (ref "LP$12") (pin "$6") (pinfunction "GND_$6") (pintype "bidirectional"))
      (node (ref "LP$13") (pin "$6") (pinfunction "GND_$6") (pintype "bidirectional"))
      (node (ref "LP$14") (pin "$6") (pinfunction "GND_$6") (pintype "bidirectional"))
      (node (ref "LP$15") (pin "$6") (pinfunction "GND_$6") (pintype "bidirectional"))
      (node (ref "LP$16") (pin "$6") (pinfunction "GND_$6") (pintype "bidirectional"))
      (node (ref "LP$17") (pin "$6") (pinfunction "GND_$6") (pintype "bidirectional"))
      (node (ref "LP$18") (pin "$6") (pinfunction "GND_$6") (pintype "bidirectional"))
      (node (ref "LP$19") (pin "$6") (pinfunction "GND_$6") (pintype "bidirectional"))
      (node (ref "LP$2") (pin "$6") (pinfunction "GND_$6") (pintype "bidirectional"))
      (node (ref "LP$20") (pin "$6") (pinfunction "GND_$6") (pintype "bidirectional"))
      (node (ref "LP$21") (pin "$6") (pinfunction "GND_$6") (pintype "bidirectional"))
      (node (ref "LP$22") (pin "$6") (pinfunction "GND_$6") (pintype "bidirectional"))
      (node (ref "LP$23") (pin "$6") (pinfunction "GND_$6") (pintype "bidirectional"))
      (node (ref "LP$24") (pin "$6") (pinfunction "GND_$6") (pintype "bidirectional"))
      (node (ref "LP$3") (pin "$6") (pinfunction "GND_$6") (pintype "bidirectional"))
      (node (ref "LP$4") (pin "$6") (pinfunction "GND_$6") (pintype "bidirectional"))
      (node (ref "LP$5") (pin "$6") (pinfunction "GND_$6") (pintype "bidirectional"))
      (node (ref "LP$6") (pin "$6") (pinfunction "GND_$6") (pintype "bidirectional"))
      (node (ref "LP$7") (pin "$6") (pinfunction "GND_$6") (pintype "bidirectional"))
      (node (ref "LP$8") (pin "$6") (pinfunction "GND_$6") (pintype "bidirectional"))
      (node (ref "LP$9") (pin "$6") (pinfunction "GND_$6") (pintype "bidirectional"))
      (node (ref "S$16") (pin "GND") (pinfunction "GND_GND") (pintype "passive"))
      (node (ref "S$16") (pin "GND@1") (pinfunction "GND_GND@1") (pintype "passive"))
      (node (ref "S$18") (pin "GND") (pinfunction "GND_GND") (pintype "passive"))
      (node (ref "S$18") (pin "GND@1") (pinfunction "GND_GND@1") (pintype "passive"))
      (node (ref "S$21") (pin "GND") (pinfunction "GND_GND") (pintype "passive"))
      (node (ref "S$21") (pin "GND@1") (pinfunction "GND_GND@1") (pintype "passive"))
      (node (ref "S$4") (pin "GND") (pinfunction "GND_GND") (pintype "passive"))
      (node (ref "S$4") (pin "GND@1") (pinfunction "GND_GND@1") (pintype "passive"))
      (node (ref "S$6") (pin "GND") (pinfunction "GND_GND") (pintype "passive"))
      (node (ref "S$6") (pin "GND@1") (pinfunction "GND_GND@1") (pintype "passive"))
      (node (ref "S$9") (pin "GND") (pinfunction "GND_GND") (pintype "passive"))
      (node (ref "S$9") (pin "GND@1") (pinfunction "GND_GND@1") (pintype "passive"))
      (node (ref "U$2") (pin "GND") (pinfunction "GND$1_GND") (pintype "bidirectional"))
      (node (ref "U$2") (pin "GND1") (pinfunction "GND$1_GND1") (pintype "bidirectional"))
      (node (ref "U$2") (pin "GND2") (pinfunction "GND$1_GND2") (pintype "bidirectional"))
      (node (ref "U$2") (pin "GND3") (pinfunction "GND$1_GND3") (pintype "bidirectional"))
      (node (ref "U$2") (pin "GND4") (pinfunction "GND$1_GND4") (pintype "bidirectional"))
      (node (ref "U$2") (pin "GND5") (pinfunction "GND$1_GND5") (pintype "bidirectional"))
      (node (ref "X1") (pin "P$25") (pinfunction "25_P$25") (pintype "passive"))
      (node (ref "X1") (pin "P$26") (pinfunction "26_P$26") (pintype "passive"))
    )
    (net (code "56") (name "Net-(S$4-Pad1)") (class "Default")
      (node (ref "S$4") (pin "1") (pinfunction "1_1") (pintype "passive"))
      (node (ref "U$4") (pin "HF") (pinfunction "HF_HF") (pintype "bidirectional"))
    )
    (net (code "57") (name "Net-(S$6-Pad1)") (class "Default")
      (node (ref "S$6") (pin "1") (pinfunction "1_1") (pintype "passive"))
      (node (ref "U$6") (pin "HF") (pinfunction "HF_HF") (pintype "bidirectional"))
    )
    (net (code "58") (name "Net-(S$9-Pad1)") (class "Default")
      (node (ref "S$9") (pin "1") (pinfunction "1_1") (pintype "passive"))
      (node (ref "U$9") (pin "HF") (pinfunction "HF_HF") (pintype "bidirectional"))
    )
    (net (code "59") (name "Net-(S$16-Pad1)") (class "Default")
      (node (ref "S$16") (pin "1") (pinfunction "1_1") (pintype "passive"))
      (node (ref "U$16") (pin "HF") (pinfunction "HF_HF") (pintype "bidirectional"))
    )
    (net (code "60") (name "Net-(S$18-Pad1)") (class "Default")
      (node (ref "S$18") (pin "1") (pinfunction "1_1") (pintype "passive"))
      (node (ref "U$18") (pin "HF") (pinfunction "HF_HF") (pintype "bidirectional"))
    )
    (net (code "61") (name "Net-(S$21-Pad1)") (class "Default")
      (node (ref "S$21") (pin "1") (pinfunction "1_1") (pintype "passive"))
      (node (ref "U$21") (pin "HF") (pinfunction "HF_HF") (pintype "bidirectional"))
    )
    (net (code "62") (name "Net-(U$2-RF$01)") (class "Default")
      (node (ref "G1") (pin "1") (pinfunction "1_1") (pintype "passive"))
      (node (ref "G2") (pin "1") (pinfunction "1_1") (pintype "passive"))
      (node (ref "U$2") (pin "RF$1") (pinfunction "RF$01_RF$1") (pintype "bidirectional"))
      (node (ref "U$2") (pin "RF$2") (pinfunction "RF$02_RF$2") (pintype "bidirectional"))
    )
  )
)
